# 6_SurvBot_RCU_CurrentFeedback.net
KiCad netlist of a schematic drawn in Altium Designer
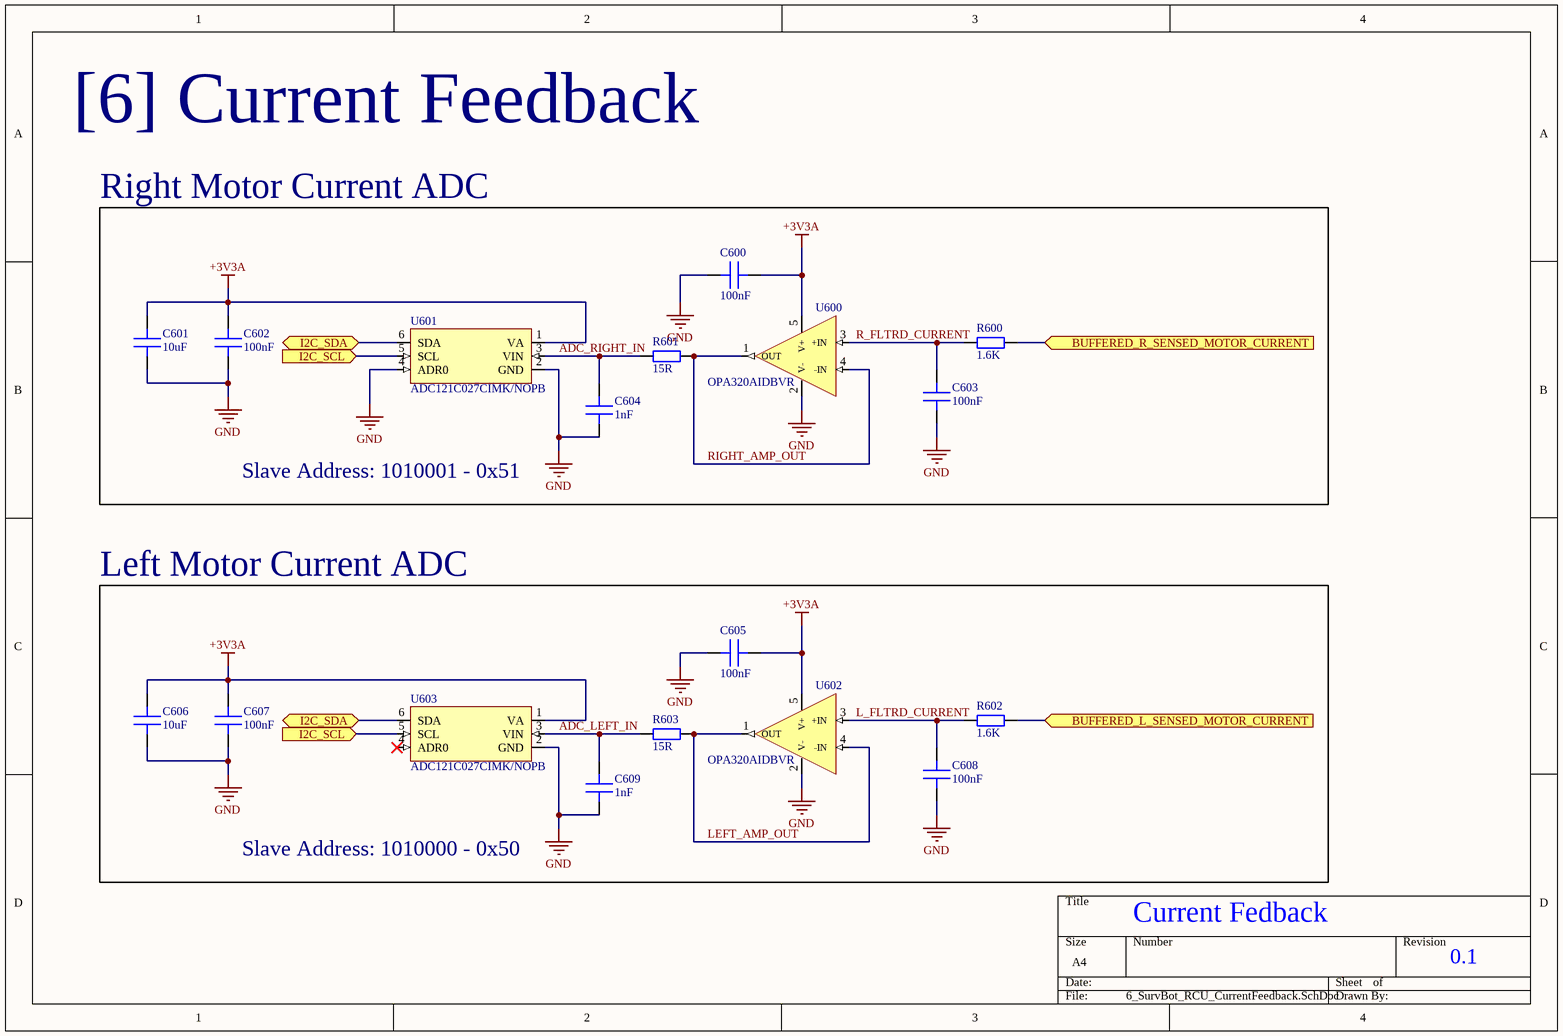
[diagram p0: 6_SurvBot_RCU_CurrentFeedback.SchDoc]

(export (version "E")
  (design (tool "Eeschema 10.0.6"))
  (components
    (comp (ref "C600")
      (value "100nF")
      (footprint "CAP_0402")
      (description "0.1 µF ±10% 10V Ceramic Capacitor X7R 0402 (1005 Metric)")
      (fields
        (field (name "MANUFACTURER") "Samsung Electro-Mechanics")
        (field (name "MANUFACTURER PART #") "CL05B104KP5NNNC")
      )
      (libsource (lib "GhaniLibrary") (part "CAP_100nF-10V-10%-0402"))
    )
    (comp (ref "C601")
      (value "10uF")
      (footprint "CAP_0402")
      (description "10 µF ±20% 10V Ceramic Capacitor X5R 0402 (1005 Metric)")
      (fields
        (field (name "MANUFACTURER") "Murata Electronics")
        (field (name "MANUFACTURER PART #") "GRM155R61A106ME11D")
      )
      (libsource (lib "GhaniLibrary") (part "CAP_10uF-10V-20%-0402"))
    )
    (comp (ref "C602")
      (value "100nF")
      (footprint "CAP_0402")
      (description "0.1 µF ±10% 10V Ceramic Capacitor X7R 0402 (1005 Metric)")
      (fields
        (field (name "MANUFACTURER") "Samsung Electro-Mechanics")
        (field (name "MANUFACTURER PART #") "CL05B104KP5NNNC")
      )
      (libsource (lib "GhaniLibrary") (part "CAP_100nF-10V-10%-0402"))
    )
    (comp (ref "C603")
      (value "100nF")
      (footprint "CAP_0603")
      (description "0.1 µF ±10% 50V Ceramic Capacitor X7R 0603 (1608 Metric)")
      (fields (field (name "MANUFACTURER") "KEMET") (field (name "MANUFACTURER PART #") "C0603C104K5RACAUTO"))
      (libsource (lib "GhaniLibrary") (part "CAP_100nF-50V-10%-0603"))
    )
    (comp (ref "C604")
      (value "1nF")
      (footprint "CAP_0402")
      (description "1000 pF ±5% 50V Ceramic Capacitor C0G, NP0 0402 (1005 Metric)")
      (fields
        (field (name "MANUFACTURER") "Murata Electronics")
        (field (name "MANUFACTURER PART #") "GRM1555C1H102JA01D")
      )
      (libsource (lib "GhaniLibrary") (part "CAP_1nF-50V-5%-0402"))
    )
    (comp (ref "C605")
      (value "100nF")
      (footprint "CAP_0402")
      (description "0.1 µF ±10% 10V Ceramic Capacitor X7R 0402 (1005 Metric)")
      (fields
        (field (name "MANUFACTURER") "Samsung Electro-Mechanics")
        (field (name "MANUFACTURER PART #") "CL05B104KP5NNNC")
      )
      (libsource (lib "GhaniLibrary") (part "CAP_100nF-10V-10%-0402"))
    )
    (comp (ref "C606")
      (value "10uF")
      (footprint "CAP_0402")
      (description "10 µF ±20% 10V Ceramic Capacitor X5R 0402 (1005 Metric)")
      (fields
        (field (name "MANUFACTURER") "Murata Electronics")
        (field (name "MANUFACTURER PART #") "GRM155R61A106ME11D")
      )
      (libsource (lib "GhaniLibrary") (part "CAP_10uF-10V-20%-0402"))
    )
    (comp (ref "C607")
      (value "100nF")
      (footprint "CAP_0402")
      (description "0.1 µF ±10% 10V Ceramic Capacitor X7R 0402 (1005 Metric)")
      (fields
        (field (name "MANUFACTURER") "Samsung Electro-Mechanics")
        (field (name "MANUFACTURER PART #") "CL05B104KP5NNNC")
      )
      (libsource (lib "GhaniLibrary") (part "CAP_100nF-10V-10%-0402"))
    )
    (comp (ref "C608")
      (value "100nF")
      (footprint "CAP_0603")
      (description "0.1 µF ±10% 50V Ceramic Capacitor X7R 0603 (1608 Metric)")
      (fields (field (name "MANUFACTURER") "KEMET") (field (name "MANUFACTURER PART #") "C0603C104K5RACAUTO"))
      (libsource (lib "GhaniLibrary") (part "CAP_100nF-50V-10%-0603"))
    )
    (comp (ref "C609")
      (value "1nF")
      (footprint "CAP_0402")
      (description "1000 pF ±5% 50V Ceramic Capacitor C0G, NP0 0402 (1005 Metric)")
      (fields
        (field (name "MANUFACTURER") "Murata Electronics")
        (field (name "MANUFACTURER PART #") "GRM1555C1H102JA01D")
      )
      (libsource (lib "GhaniLibrary") (part "CAP_1nF-50V-5%-0402"))
    )
    (comp (ref "R600")
      (value "1.6K")
      (footprint "RES_0603")
      (description "1.6 kOhms ±1% 0.1W, 1/10W Chip Resistor 0603 (1608 Metric) Moisture Resistant Thick Film")
      (fields (field (name "MANUFACTURER") "BOURNS") (field (name "MANUFACTURER PART #") "CR0603-FX-1601ELF"))
      (libsource (lib "GhaniLibrary") (part "RES_1.6K-100mW-1%-0603"))
    )
    (comp (ref "R601")
      (value "15R")
      (footprint "RES_0603")
      (description "15 Ohms ±1% 0.1W, 1/10W Chip Resistor 0603 (1608 Metric) Automotive AEC-Q200 Thick Film")
      (fields (field (name "MANUFACTURER") "PANASONIC") (field (name "MANUFACTURER PART #") "ERJ3EKF15R0V"))
      (libsource (lib "GhaniLibrary") (part "RES_15R-100mW-1%-0603"))
    )
    (comp (ref "R602")
      (value "1.6K")
      (footprint "RES_0603")
      (description "1.6 kOhms ±1% 0.1W, 1/10W Chip Resistor 0603 (1608 Metric) Moisture Resistant Thick Film")
      (fields (field (name "MANUFACTURER") "BOURNS") (field (name "MANUFACTURER PART #") "CR0603-FX-1601ELF"))
      (libsource (lib "GhaniLibrary") (part "RES_1.6K-100mW-1%-0603"))
    )
    (comp (ref "R603")
      (value "15R")
      (footprint "RES_0603")
      (description "15 Ohms ±1% 0.1W, 1/10W Chip Resistor 0603 (1608 Metric) Automotive AEC-Q200 Thick Film")
      (fields (field (name "MANUFACTURER") "PANASONIC") (field (name "MANUFACTURER PART #") "ERJ3EKF15R0V"))
      (libsource (lib "GhaniLibrary") (part "RES_15R-100mW-1%-0603"))
    )
    (comp (ref "U600")
      (value "OPA320AIDBVR")
      (footprint "SOT-23-5")
      (description "General Purpose Amplifier 1 Circuit Rail-to-Rail SOT-23-5")
      (fields (field (name "MANUFACTURER") "Texas Instruments"))
      (libsource (lib "GhaniLibrary") (part "OPAMP-OPA320_R2R_SOT23-5"))
    )
    (comp (ref "U601")
      (value "ADC121C027CIMK/NOPB")
      (footprint "SOT-23-6 Thin, TSOT-23-6")
      (description "12 Bit Analog to Digital Converter 1 Input 1 SAR TSOT-23-6")
      (fields (field (name "MANUFACTURER") "Texas Instruments"))
      (libsource (lib "GhaniLibrary") (part "IC_ADC121C027CIMK/NOPB"))
    )
    (comp (ref "U602")
      (value "OPA320AIDBVR")
      (footprint "SOT-23-5")
      (description "General Purpose Amplifier 1 Circuit Rail-to-Rail SOT-23-5")
      (fields (field (name "MANUFACTURER") "Texas Instruments"))
      (libsource (lib "GhaniLibrary") (part "OPAMP-OPA320_R2R_SOT23-5"))
    )
    (comp (ref "U603")
      (value "ADC121C027CIMK/NOPB")
      (footprint "SOT-23-6 Thin, TSOT-23-6")
      (description "12 Bit Analog to Digital Converter 1 Input 1 SAR TSOT-23-6")
      (fields (field (name "MANUFACTURER") "Texas Instruments"))
      (libsource (lib "GhaniLibrary") (part "IC_ADC121C027CIMK/NOPB"))
    )
  )
  (nets
    (net (code "1") (name "+3V3A") (class "Default")
      (node (ref "C600") (pin "2") (pinfunction "0_2") (pintype "passive"))
      (node (ref "C601") (pin "2") (pinfunction "0_2") (pintype "passive"))
      (node (ref "C602") (pin "2") (pinfunction "0_2") (pintype "passive"))
      (node (ref "C605") (pin "2") (pinfunction "0_2") (pintype "passive"))
      (node (ref "C606") (pin "2") (pinfunction "0_2") (pintype "passive"))
      (node (ref "C607") (pin "2") (pinfunction "0_2") (pintype "passive"))
      (node (ref "U600") (pin "5") (pinfunction "V+_5") (pintype "power_in"))
      (node (ref "U601") (pin "1") (pinfunction "VA_1") (pintype "power_in"))
      (node (ref "U602") (pin "5") (pinfunction "V+_5") (pintype "power_in"))
      (node (ref "U603") (pin "1") (pinfunction "VA_1") (pintype "power_in"))
    )
    (net (code "2") (name "/ADC_LEFT_IN") (class "Default")
      (node (ref "C609") (pin "2") (pinfunction "0_2") (pintype "passive"))
      (node (ref "R603") (pin "1") (pinfunction "1_1") (pintype "passive"))
      (node (ref "U603") (pin "3") (pinfunction "VIN_3") (pintype "input"))
    )
    (net (code "3") (name "/ADC_RIGHT_IN") (class "Default")
      (node (ref "C604") (pin "2") (pinfunction "0_2") (pintype "passive"))
      (node (ref "R601") (pin "1") (pinfunction "1_1") (pintype "passive"))
      (node (ref "U601") (pin "3") (pinfunction "VIN_3") (pintype "input"))
    )
    (net (code "4") (name "/BUFFERED_L_SENSED_MOTOR_CURRENT") (class "Default")
      (node (ref "R602") (pin "2") (pinfunction "2_2") (pintype "passive"))
    )
    (net (code "5") (name "/BUFFERED_R_SENSED_MOTOR_CURRENT") (class "Default")
      (node (ref "R600") (pin "2") (pinfunction "2_2") (pintype "passive"))
    )
    (net (code "6") (name "/I2C_SCL") (class "Default")
      (node (ref "U601") (pin "5") (pinfunction "SCL_5") (pintype "input"))
      (node (ref "U603") (pin "5") (pinfunction "SCL_5") (pintype "input"))
    )
    (net (code "7") (name "/I2C_SDA") (class "Default")
      (node (ref "U601") (pin "6") (pinfunction "SDA_6") (pintype "bidirectional"))
      (node (ref "U603") (pin "6") (pinfunction "SDA_6") (pintype "bidirectional"))
    )
    (net (code "8") (name "/LEFT_AMP_OUT") (class "Default")
      (node (ref "R603") (pin "2") (pinfunction "2_2") (pintype "passive"))
      (node (ref "U602") (pin "1") (pinfunction "OUT_1") (pintype "output"))
      (node (ref "U602") (pin "4") (pinfunction "-IN_4") (pintype "input"))
    )
    (net (code "9") (name "/L_FLTRD_CURRENT") (class "Default")
      (node (ref "C608") (pin "2") (pinfunction "0_2") (pintype "passive"))
      (node (ref "R602") (pin "1") (pinfunction "1_1") (pintype "passive"))
      (node (ref "U602") (pin "3") (pinfunction "+IN_3") (pintype "input"))
    )
    (net (code "10") (name "/RIGHT_AMP_OUT") (class "Default")
      (node (ref "R601") (pin "2") (pinfunction "2_2") (pintype "passive"))
      (node (ref "U600") (pin "1") (pinfunction "OUT_1") (pintype "output"))
      (node (ref "U600") (pin "4") (pinfunction "-IN_4") (pintype "input"))
    )
    (net (code "11") (name "/R_FLTRD_CURRENT") (class "Default")
      (node (ref "C603") (pin "2") (pinfunction "0_2") (pintype "passive"))
      (node (ref "R600") (pin "1") (pinfunction "1_1") (pintype "passive"))
      (node (ref "U600") (pin "3") (pinfunction "+IN_3") (pintype "input"))
    )
    (net (code "12") (name "GND") (class "Default")
      (node (ref "C600") (pin "1") (pinfunction "0_1") (pintype "passive"))
      (node (ref "C601") (pin "1") (pinfunction "0_1") (pintype "passive"))
      (node (ref "C602") (pin "1") (pinfunction "0_1") (pintype "passive"))
      (node (ref "C603") (pin "1") (pinfunction "0_1") (pintype "passive"))
      (node (ref "C604") (pin "1") (pinfunction "0_1") (pintype "passive"))
      (node (ref "C605") (pin "1") (pinfunction "0_1") (pintype "passive"))
      (node (ref "C606") (pin "1") (pinfunction "0_1") (pintype "passive"))
      (node (ref "C607") (pin "1") (pinfunction "0_1") (pintype "passive"))
      (node (ref "C608") (pin "1") (pinfunction "0_1") (pintype "passive"))
      (node (ref "C609") (pin "1") (pinfunction "0_1") (pintype "passive"))
      (node (ref "U600") (pin "2") (pinfunction "V-_2") (pintype "power_in"))
      (node (ref "U601") (pin "2") (pinfunction "GND_2") (pintype "power_in"))
      (node (ref "U601") (pin "4") (pinfunction "ADR0_4") (pintype "input"))
      (node (ref "U602") (pin "2") (pinfunction "V-_2") (pintype "power_in"))
      (node (ref "U603") (pin "2") (pinfunction "GND_2") (pintype "power_in"))
    )
    (net (code "13") (name "unconnected-(U603-ADR0-Pad4)") (class "Default")
      (node (ref "U603") (pin "4") (pinfunction "ADR0_4") (pintype "input+no_connect"))
    )
  )
)
